# Noctua2.net
KiCad netlist of a schematic drawn in EAGLE
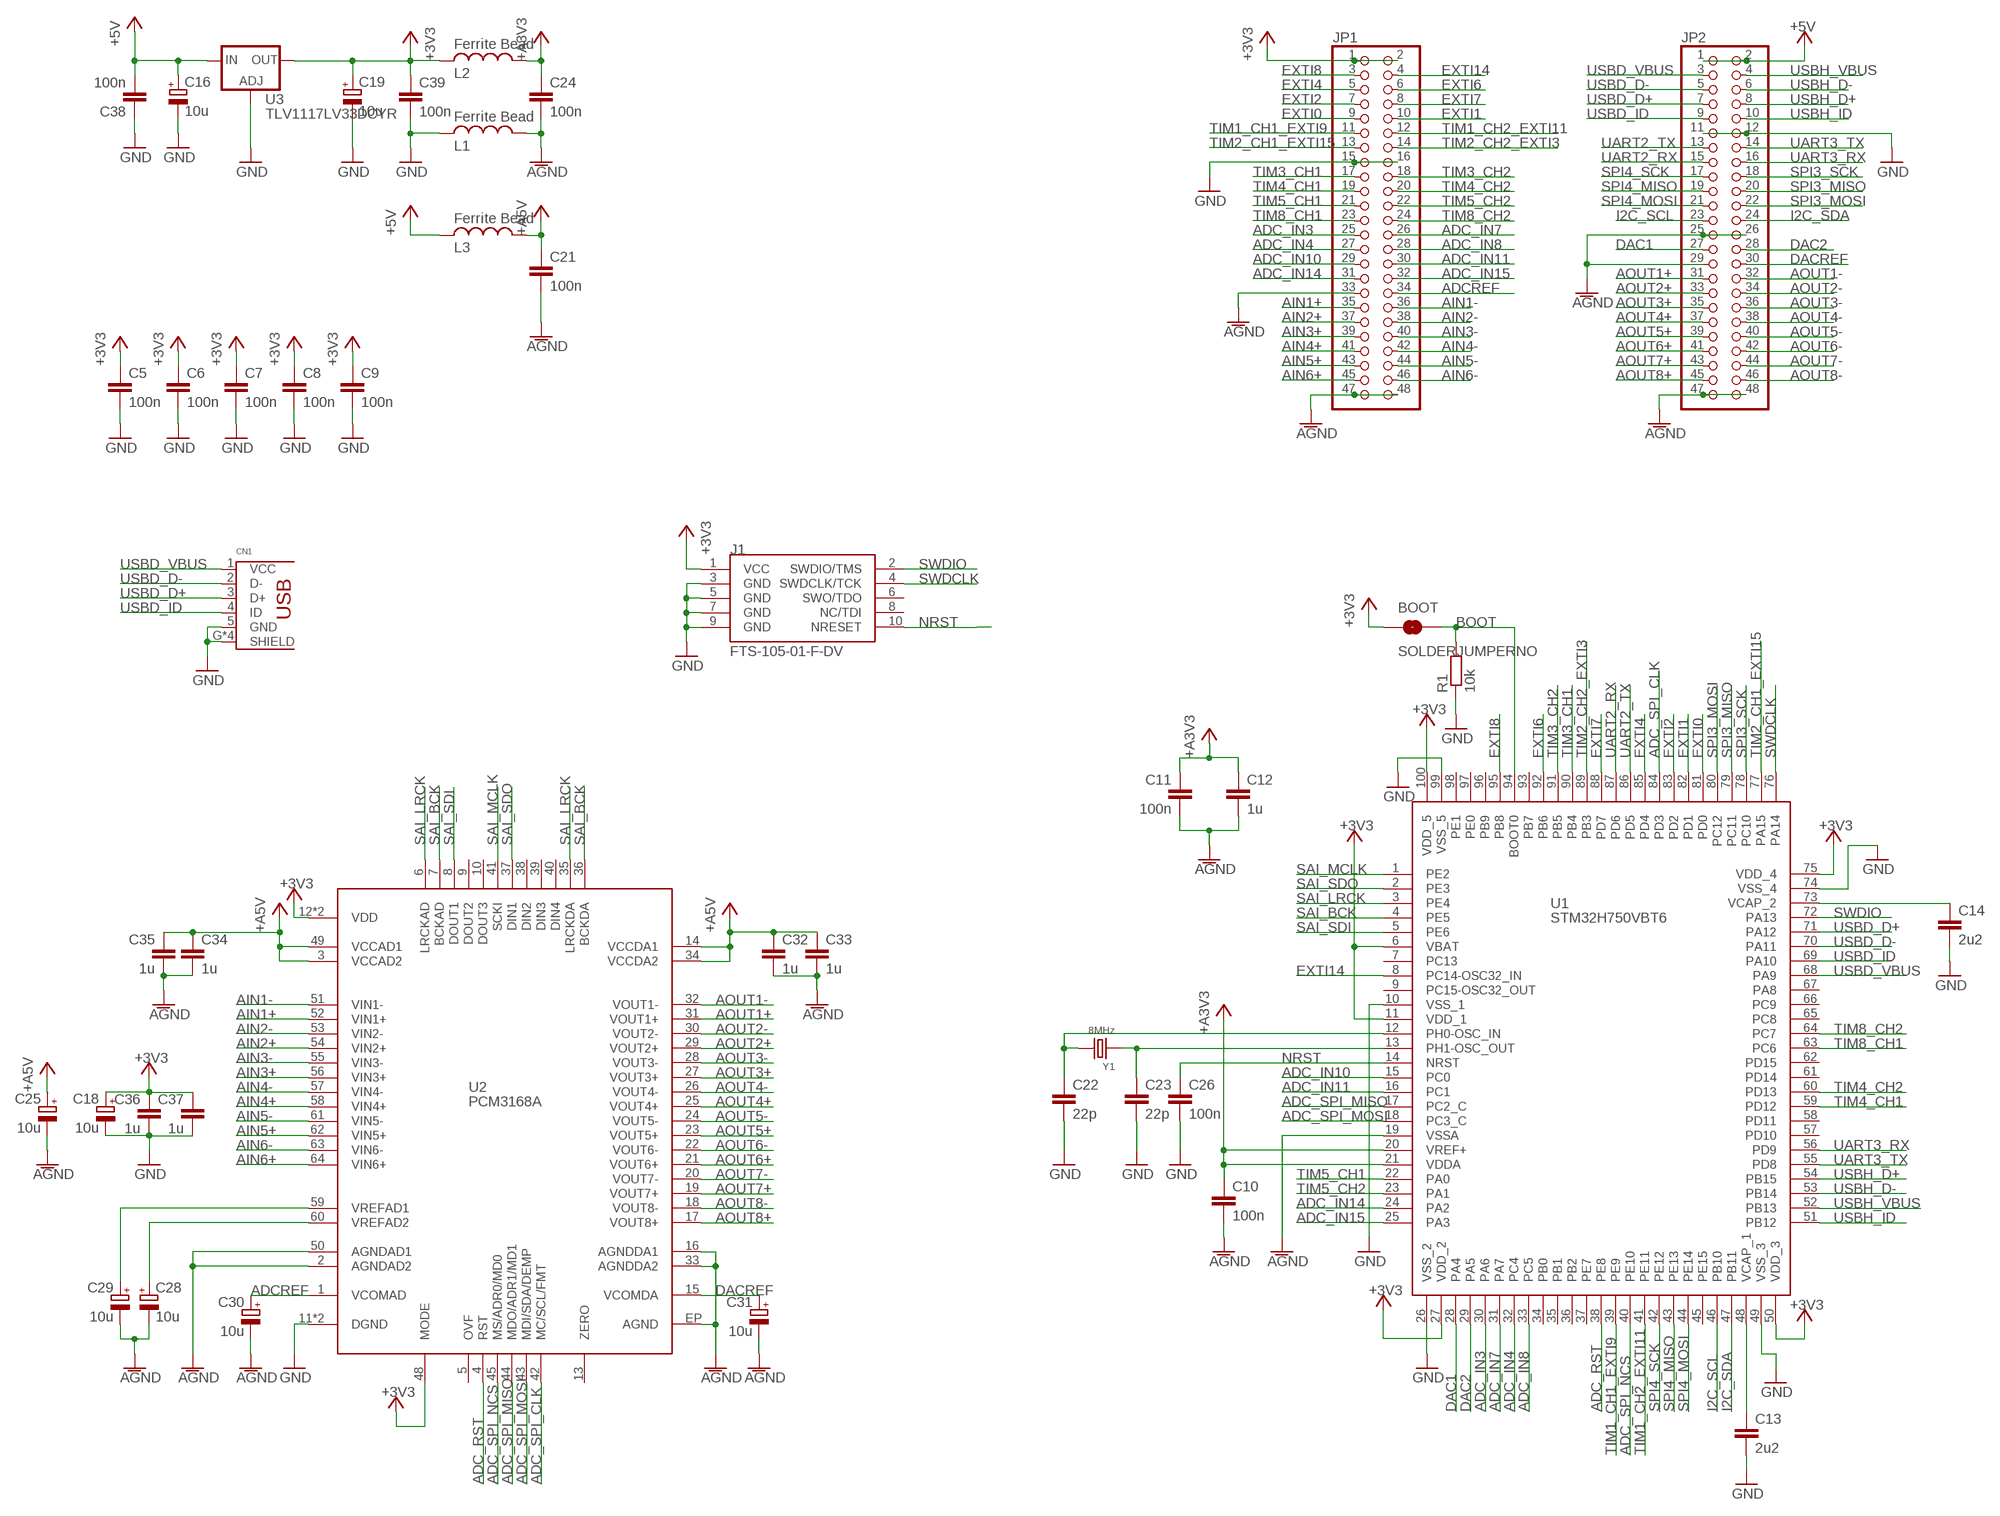
[diagram p0: schematic, sheet 1]

(export (version "E")
  (design (tool "Eeschema 10.0.6"))
  (components
    (comp (ref "BOOT")
      (value "SOLDERJUMPERNO")
      (footprint "eagle-import:SJ_2S-NO")
      (libsource (lib "eagle-import") (part "SOLDERJUMPERNO"))
    )
    (comp (ref "C5")
      (value "100n")
      (footprint "eagle-import:C0603")
      (libsource (lib "eagle-import") (part "C-EUC0603"))
    )
    (comp (ref "C6")
      (value "100n")
      (footprint "eagle-import:C0603")
      (libsource (lib "eagle-import") (part "C-EUC0603"))
    )
    (comp (ref "C7")
      (value "100n")
      (footprint "eagle-import:C0603")
      (libsource (lib "eagle-import") (part "C-EUC0603"))
    )
    (comp (ref "C8")
      (value "100n")
      (footprint "eagle-import:C0603")
      (libsource (lib "eagle-import") (part "C-EUC0603"))
    )
    (comp (ref "C9")
      (value "100n")
      (footprint "eagle-import:C0603")
      (libsource (lib "eagle-import") (part "C-EUC0603"))
    )
    (comp (ref "C10")
      (value "100n")
      (footprint "eagle-import:C0603")
      (libsource (lib "eagle-import") (part "C-EUC0603"))
    )
    (comp (ref "C11")
      (value "100n")
      (footprint "eagle-import:C0603")
      (libsource (lib "eagle-import") (part "C-EUC0603"))
    )
    (comp (ref "C12")
      (value "1u")
      (footprint "eagle-import:C0603")
      (libsource (lib "eagle-import") (part "C-EUC0603"))
    )
    (comp (ref "C13")
      (value "2u2")
      (footprint "eagle-import:C0603")
      (libsource (lib "eagle-import") (part "C-EUC0603"))
    )
    (comp (ref "C14")
      (value "2u2")
      (footprint "eagle-import:C0603")
      (libsource (lib "eagle-import") (part "C-EUC0603"))
    )
    (comp (ref "C16")
      (value "10u")
      (footprint "eagle-import:UD-4X5,8_NICHICON")
      (libsource (lib "eagle-import") (part "CPOL-EUUD-4X5,8"))
    )
    (comp (ref "C18")
      (value "10u")
      (footprint "eagle-import:UD-4X5,8_NICHICON")
      (libsource (lib "eagle-import") (part "CPOL-EUUD-4X5,8"))
    )
    (comp (ref "C19")
      (value "10u")
      (footprint "eagle-import:UD-4X5,8_NICHICON")
      (libsource (lib "eagle-import") (part "CPOL-EUUD-4X5,8"))
    )
    (comp (ref "C21")
      (value "100n")
      (footprint "eagle-import:C0603")
      (libsource (lib "eagle-import") (part "C-EUC0603"))
    )
    (comp (ref "C22")
      (value "22p")
      (footprint "eagle-import:C0603")
      (libsource (lib "eagle-import") (part "C-EUC0603"))
    )
    (comp (ref "C23")
      (value "22p")
      (footprint "eagle-import:C0603")
      (libsource (lib "eagle-import") (part "C-EUC0603"))
    )
    (comp (ref "C24")
      (value "100n")
      (footprint "eagle-import:C0603")
      (libsource (lib "eagle-import") (part "C-EUC0603"))
    )
    (comp (ref "C25")
      (value "10u")
      (footprint "eagle-import:UD-4X5,8_NICHICON")
      (libsource (lib "eagle-import") (part "CPOL-EUUD-4X5,8"))
    )
    (comp (ref "C26")
      (value "100n")
      (footprint "eagle-import:C0603")
      (libsource (lib "eagle-import") (part "C-EUC0603"))
    )
    (comp (ref "C28")
      (value "10u")
      (footprint "eagle-import:UD-4X5,8_NICHICON")
      (libsource (lib "eagle-import") (part "CPOL-EUUD-4X5,8"))
    )
    (comp (ref "C29")
      (value "10u")
      (footprint "eagle-import:UD-4X5,8_NICHICON")
      (libsource (lib "eagle-import") (part "CPOL-EUUD-4X5,8"))
    )
    (comp (ref "C30")
      (value "10u")
      (footprint "eagle-import:UD-4X5,8_NICHICON")
      (libsource (lib "eagle-import") (part "CPOL-EUUD-4X5,8"))
    )
    (comp (ref "C31")
      (value "10u")
      (footprint "eagle-import:UD-4X5,8_NICHICON")
      (libsource (lib "eagle-import") (part "CPOL-EUUD-4X5,8"))
    )
    (comp (ref "C32")
      (value "1u")
      (footprint "eagle-import:C0603")
      (libsource (lib "eagle-import") (part "C-EUC0603"))
    )
    (comp (ref "C33")
      (value "1u")
      (footprint "eagle-import:C0603")
      (libsource (lib "eagle-import") (part "C-EUC0603"))
    )
    (comp (ref "C34")
      (value "1u")
      (footprint "eagle-import:C0603")
      (libsource (lib "eagle-import") (part "C-EUC0603"))
    )
    (comp (ref "C35")
      (value "1u")
      (footprint "eagle-import:C0603")
      (libsource (lib "eagle-import") (part "C-EUC0603"))
    )
    (comp (ref "C36")
      (value "1u")
      (footprint "eagle-import:C0603")
      (libsource (lib "eagle-import") (part "C-EUC0603"))
    )
    (comp (ref "C37")
      (value "1u")
      (footprint "eagle-import:C0603")
      (libsource (lib "eagle-import") (part "C-EUC0603"))
    )
    (comp (ref "C38")
      (value "100n")
      (footprint "eagle-import:C0603")
      (libsource (lib "eagle-import") (part "C-EUC0603"))
    )
    (comp (ref "C39")
      (value "100n")
      (footprint "eagle-import:C0603")
      (libsource (lib "eagle-import") (part "C-EUC0603"))
    )
    (comp (ref "CN1")
      (value "USB_HRS_ZX62-B-5PA(11)MICRO.B")
      (footprint "eagle-import:HRS_ZX62RD-AB-5P8")
      (libsource (lib "eagle-import") (part "USB_HRS_ZX62-B-5PA(11)MICRO.B"))
    )
    (comp (ref "J1")
      (value "FTS-105-01-F-DV")
      (footprint "eagle-import:2X5_1.27MM_SMD")
      (libsource (lib "eagle-import") (part "ARM_10SMD"))
    )
    (comp (ref "JP1")
      (value "PINHD-2X24")
      (footprint "eagle-import:2X24")
      (libsource (lib "eagle-import") (part "PINHD-2X24"))
    )
    (comp (ref "JP2")
      (value "PINHD-2X24")
      (footprint "eagle-import:2X24")
      (libsource (lib "eagle-import") (part "PINHD-2X24"))
    )
    (comp (ref "L1")
      (value "Ferrite Bead")
      (footprint "eagle-import:0603")
      (libsource (lib "eagle-import") (part "INDUCTOR"))
    )
    (comp (ref "L2")
      (value "Ferrite Bead")
      (footprint "eagle-import:0603")
      (libsource (lib "eagle-import") (part "INDUCTOR"))
    )
    (comp (ref "L3")
      (value "Ferrite Bead")
      (footprint "eagle-import:0603")
      (libsource (lib "eagle-import") (part "INDUCTOR"))
    )
    (comp (ref "R1")
      (value "10k")
      (footprint "eagle-import:0603@1")
      (libsource (lib "eagle-import") (part "R-EU_0603"))
    )
    (comp (ref "U1")
      (value "STM32H750VBT6")
      (footprint "eagle-import:QFP50P1600X1600X160-100N")
      (fields (field (name "MOUSER_PART_NUMBER") "511-STM32H750VBT6"))
      (libsource (lib "eagle-import") (part "STM32H750VBT6"))
    )
    (comp (ref "U2")
      (value "PCM3168A")
      (footprint "eagle-import:PQFP64")
      (libsource (lib "eagle-import") (part "PCM3168A"))
    )
    (comp (ref "U3")
      (value "TLV1117LV33DCYR")
      (footprint "eagle-import:SOT223")
      (libsource (lib "eagle-import") (part "LD117A?S33TR"))
    )
    (comp (ref "Y1")
      (value "8MHz")
      (footprint "eagle-import:X2-SMD-5.0X3.2X1.3MM")
      (fields (field (name "MPN") "5032/2P"))
      (libsource (lib "eagle-import") (part "SMD-CRYSTAL-8MHZ-20PF-20PPM(2P-5.0X3.2MM)"))
    )
  )
  (nets
    (net (code "1") (name "+3V3") (class "Default")
      (node (ref "BOOT") (pin "1") (pinfunction "1_1") (pintype "passive"))
      (node (ref "C18") (pin "+") (pinfunction "+_+") (pintype "passive"))
      (node (ref "C19") (pin "+") (pinfunction "+_+") (pintype "passive"))
      (node (ref "C36") (pin "1") (pinfunction "1_1") (pintype "passive"))
      (node (ref "C37") (pin "1") (pinfunction "1_1") (pintype "passive"))
      (node (ref "C39") (pin "1") (pinfunction "1_1") (pintype "passive"))
      (node (ref "C5") (pin "1") (pinfunction "1_1") (pintype "passive"))
      (node (ref "C6") (pin "1") (pinfunction "1_1") (pintype "passive"))
      (node (ref "C7") (pin "1") (pinfunction "1_1") (pintype "passive"))
      (node (ref "C8") (pin "1") (pinfunction "1_1") (pintype "passive"))
      (node (ref "C9") (pin "1") (pinfunction "1_1") (pintype "passive"))
      (node (ref "J1") (pin "1") (pinfunction "VCC_1") (pintype "bidirectional"))
      (node (ref "JP1") (pin "1") (pinfunction "1_1") (pintype "passive"))
      (node (ref "JP1") (pin "2") (pinfunction "2_2") (pintype "passive"))
      (node (ref "L2") (pin "2") (pinfunction "2_2") (pintype "passive"))
      (node (ref "U1") (pin "100") (pinfunction "VDD_5_100") (pintype "bidirectional"))
      (node (ref "U1") (pin "11") (pinfunction "VDD_1_11") (pintype "bidirectional"))
      (node (ref "U1") (pin "27") (pinfunction "VDD_2_27") (pintype "bidirectional"))
      (node (ref "U1") (pin "50") (pinfunction "VDD_3_50") (pintype "bidirectional"))
      (node (ref "U1") (pin "6") (pinfunction "VBAT_6") (pintype "bidirectional"))
      (node (ref "U1") (pin "75") (pinfunction "VDD_4_75") (pintype "bidirectional"))
      (node (ref "U2") (pin "12") (pinfunction "VDD_12") (pintype "bidirectional"))
      (node (ref "U2") (pin "46") (pinfunction "VDD_46") (pintype "bidirectional"))
      (node (ref "U2") (pin "48") (pinfunction "MODE_48") (pintype "bidirectional"))
      (node (ref "U3") (pin "4") (pinfunction "OUT_4") (pintype "passive"))
    )
    (net (code "2") (name "+5V") (class "Default")
      (node (ref "C16") (pin "+") (pinfunction "+_+") (pintype "passive"))
      (node (ref "C38") (pin "2") (pinfunction "2_2") (pintype "passive"))
      (node (ref "JP2") (pin "1") (pinfunction "1_1") (pintype "passive"))
      (node (ref "JP2") (pin "2") (pinfunction "2_2") (pintype "passive"))
      (node (ref "L3") (pin "2") (pinfunction "2_2") (pintype "passive"))
      (node (ref "U3") (pin "3") (pinfunction "IN_3") (pintype "input"))
    )
    (net (code "3") (name "+A3V3") (class "Default")
      (node (ref "C10") (pin "1") (pinfunction "1_1") (pintype "passive"))
      (node (ref "C11") (pin "1") (pinfunction "1_1") (pintype "passive"))
      (node (ref "C12") (pin "1") (pinfunction "1_1") (pintype "passive"))
      (node (ref "C24") (pin "1") (pinfunction "1_1") (pintype "passive"))
      (node (ref "L2") (pin "1") (pinfunction "1_1") (pintype "passive"))
      (node (ref "U1") (pin "20") (pinfunction "VREF+_20") (pintype "bidirectional"))
      (node (ref "U1") (pin "21") (pinfunction "VDDA_21") (pintype "bidirectional"))
    )
    (net (code "4") (name "+A5V") (class "Default")
      (node (ref "C21") (pin "1") (pinfunction "1_1") (pintype "passive"))
      (node (ref "C25") (pin "+") (pinfunction "+_+") (pintype "passive"))
      (node (ref "C32") (pin "1") (pinfunction "1_1") (pintype "passive"))
      (node (ref "C33") (pin "1") (pinfunction "1_1") (pintype "passive"))
      (node (ref "C34") (pin "1") (pinfunction "1_1") (pintype "passive"))
      (node (ref "C35") (pin "1") (pinfunction "1_1") (pintype "passive"))
      (node (ref "L3") (pin "1") (pinfunction "1_1") (pintype "passive"))
      (node (ref "U2") (pin "14") (pinfunction "VCCDA1_14") (pintype "bidirectional"))
      (node (ref "U2") (pin "3") (pinfunction "VCCAD2_3") (pintype "bidirectional"))
      (node (ref "U2") (pin "34") (pinfunction "VCCDA2_34") (pintype "bidirectional"))
      (node (ref "U2") (pin "49") (pinfunction "VCCAD1_49") (pintype "bidirectional"))
    )
    (net (code "5") (name "/ADCREF") (class "Default")
      (node (ref "C30") (pin "+") (pinfunction "+_+") (pintype "passive"))
      (node (ref "JP1") (pin "34") (pinfunction "34_34") (pintype "passive"))
      (node (ref "U2") (pin "1") (pinfunction "VCOMAD_1") (pintype "bidirectional"))
    )
    (net (code "6") (name "/ADC_IN3") (class "Default")
      (node (ref "JP1") (pin "25") (pinfunction "25_25") (pintype "passive"))
      (node (ref "U1") (pin "30") (pinfunction "PA6_30") (pintype "bidirectional"))
    )
    (net (code "7") (name "/ADC_IN4") (class "Default")
      (node (ref "JP1") (pin "27") (pinfunction "27_27") (pintype "passive"))
      (node (ref "U1") (pin "32") (pinfunction "PC4_32") (pintype "bidirectional"))
    )
    (net (code "8") (name "/ADC_IN7") (class "Default")
      (node (ref "JP1") (pin "26") (pinfunction "26_26") (pintype "passive"))
      (node (ref "U1") (pin "31") (pinfunction "PA7_31") (pintype "bidirectional"))
    )
    (net (code "9") (name "/ADC_IN8") (class "Default")
      (node (ref "JP1") (pin "28") (pinfunction "28_28") (pintype "passive"))
      (node (ref "U1") (pin "33") (pinfunction "PC5_33") (pintype "bidirectional"))
    )
    (net (code "10") (name "/ADC_IN10") (class "Default")
      (node (ref "JP1") (pin "29") (pinfunction "29_29") (pintype "passive"))
      (node (ref "U1") (pin "15") (pinfunction "PC0_15") (pintype "bidirectional"))
    )
    (net (code "11") (name "/ADC_IN11") (class "Default")
      (node (ref "JP1") (pin "30") (pinfunction "30_30") (pintype "passive"))
      (node (ref "U1") (pin "16") (pinfunction "PC1_16") (pintype "bidirectional"))
    )
    (net (code "12") (name "/ADC_IN14") (class "Default")
      (node (ref "JP1") (pin "31") (pinfunction "31_31") (pintype "passive"))
      (node (ref "U1") (pin "24") (pinfunction "PA2_24") (pintype "bidirectional"))
    )
    (net (code "13") (name "/ADC_IN15") (class "Default")
      (node (ref "JP1") (pin "32") (pinfunction "32_32") (pintype "passive"))
      (node (ref "U1") (pin "25") (pinfunction "PA3_25") (pintype "bidirectional"))
    )
    (net (code "14") (name "/ADC_RST") (class "Default")
      (node (ref "U1") (pin "38") (pinfunction "PE8_38") (pintype "bidirectional"))
      (node (ref "U2") (pin "4") (pinfunction "RST_4") (pintype "bidirectional"))
    )
    (net (code "15") (name "/ADC_SPI_CLK") (class "Default")
      (node (ref "U1") (pin "84") (pinfunction "PD3_84") (pintype "bidirectional"))
      (node (ref "U2") (pin "42") (pinfunction "MC/SCL/FMT_42") (pintype "bidirectional"))
    )
    (net (code "16") (name "/ADC_SPI_MISO") (class "Default")
      (node (ref "U1") (pin "17") (pinfunction "PC2_C_17") (pintype "bidirectional"))
      (node (ref "U2") (pin "44") (pinfunction "MDO/ADR1/MD1_44") (pintype "bidirectional"))
    )
    (net (code "17") (name "/ADC_SPI_MOSI") (class "Default")
      (node (ref "U1") (pin "18") (pinfunction "PC3_C_18") (pintype "bidirectional"))
      (node (ref "U2") (pin "43") (pinfunction "MDI/SDA/DEMP_43") (pintype "bidirectional"))
    )
    (net (code "18") (name "/ADC_SPI_NCS") (class "Default")
      (node (ref "U1") (pin "40") (pinfunction "PE10_40") (pintype "bidirectional"))
      (node (ref "U2") (pin "45") (pinfunction "MS/ADR0/MD0_45") (pintype "bidirectional"))
    )
    (net (code "19") (name "/AIN1+") (class "Default")
      (node (ref "JP1") (pin "35") (pinfunction "35_35") (pintype "passive"))
      (node (ref "U2") (pin "52") (pinfunction "VIN1+_52") (pintype "bidirectional"))
    )
    (net (code "20") (name "/AIN1-") (class "Default")
      (node (ref "JP1") (pin "36") (pinfunction "36_36") (pintype "passive"))
      (node (ref "U2") (pin "51") (pinfunction "VIN1-_51") (pintype "bidirectional"))
    )
    (net (code "21") (name "/AIN2+") (class "Default")
      (node (ref "JP1") (pin "37") (pinfunction "37_37") (pintype "passive"))
      (node (ref "U2") (pin "54") (pinfunction "VIN2+_54") (pintype "bidirectional"))
    )
    (net (code "22") (name "/AIN2-") (class "Default")
      (node (ref "JP1") (pin "38") (pinfunction "38_38") (pintype "passive"))
      (node (ref "U2") (pin "53") (pinfunction "VIN2-_53") (pintype "bidirectional"))
    )
    (net (code "23") (name "/AIN3+") (class "Default")
      (node (ref "JP1") (pin "39") (pinfunction "39_39") (pintype "passive"))
      (node (ref "U2") (pin "56") (pinfunction "VIN3+_56") (pintype "bidirectional"))
    )
    (net (code "24") (name "/AIN3-") (class "Default")
      (node (ref "JP1") (pin "40") (pinfunction "40_40") (pintype "passive"))
      (node (ref "U2") (pin "55") (pinfunction "VIN3-_55") (pintype "bidirectional"))
    )
    (net (code "25") (name "/AIN4+") (class "Default")
      (node (ref "JP1") (pin "41") (pinfunction "41_41") (pintype "passive"))
      (node (ref "U2") (pin "58") (pinfunction "VIN4+_58") (pintype "bidirectional"))
    )
    (net (code "26") (name "/AIN4-") (class "Default")
      (node (ref "JP1") (pin "42") (pinfunction "42_42") (pintype "passive"))
      (node (ref "U2") (pin "57") (pinfunction "VIN4-_57") (pintype "bidirectional"))
    )
    (net (code "27") (name "/AIN5+") (class "Default")
      (node (ref "JP1") (pin "43") (pinfunction "43_43") (pintype "passive"))
      (node (ref "U2") (pin "62") (pinfunction "VIN5+_62") (pintype "bidirectional"))
    )
    (net (code "28") (name "/AIN5-") (class "Default")
      (node (ref "JP1") (pin "44") (pinfunction "44_44") (pintype "passive"))
      (node (ref "U2") (pin "61") (pinfunction "VIN5-_61") (pintype "bidirectional"))
    )
    (net (code "29") (name "/AIN6+") (class "Default")
      (node (ref "JP1") (pin "45") (pinfunction "45_45") (pintype "passive"))
      (node (ref "U2") (pin "64") (pinfunction "VIN6+_64") (pintype "bidirectional"))
    )
    (net (code "30") (name "/AIN6-") (class "Default")
      (node (ref "JP1") (pin "46") (pinfunction "46_46") (pintype "passive"))
      (node (ref "U2") (pin "63") (pinfunction "VIN6-_63") (pintype "bidirectional"))
    )
    (net (code "31") (name "/AOUT1+") (class "Default")
      (node (ref "JP2") (pin "31") (pinfunction "31_31") (pintype "passive"))
      (node (ref "U2") (pin "31") (pinfunction "VOUT1+_31") (pintype "bidirectional"))
    )
    (net (code "32") (name "/AOUT1-") (class "Default")
      (node (ref "JP2") (pin "32") (pinfunction "32_32") (pintype "passive"))
      (node (ref "U2") (pin "32") (pinfunction "VOUT1-_32") (pintype "bidirectional"))
    )
    (net (code "33") (name "/AOUT2+") (class "Default")
      (node (ref "JP2") (pin "33") (pinfunction "33_33") (pintype "passive"))
      (node (ref "U2") (pin "29") (pinfunction "VOUT2+_29") (pintype "bidirectional"))
    )
    (net (code "34") (name "/AOUT2-") (class "Default")
      (node (ref "JP2") (pin "34") (pinfunction "34_34") (pintype "passive"))
      (node (ref "U2") (pin "30") (pinfunction "VOUT2-_30") (pintype "bidirectional"))
    )
    (net (code "35") (name "/AOUT3+") (class "Default")
      (node (ref "JP2") (pin "35") (pinfunction "35_35") (pintype "passive"))
      (node (ref "U2") (pin "27") (pinfunction "VOUT3+_27") (pintype "bidirectional"))
    )
    (net (code "36") (name "/AOUT3-") (class "Default")
      (node (ref "JP2") (pin "36") (pinfunction "36_36") (pintype "passive"))
      (node (ref "U2") (pin "28") (pinfunction "VOUT3-_28") (pintype "bidirectional"))
    )
    (net (code "37") (name "/AOUT4+") (class "Default")
      (node (ref "JP2") (pin "37") (pinfunction "37_37") (pintype "passive"))
      (node (ref "U2") (pin "25") (pinfunction "VOUT4+_25") (pintype "bidirectional"))
    )
    (net (code "38") (name "/AOUT4-") (class "Default")
      (node (ref "JP2") (pin "38") (pinfunction "38_38") (pintype "passive"))
      (node (ref "U2") (pin "26") (pinfunction "VOUT4-_26") (pintype "bidirectional"))
    )
    (net (code "39") (name "/AOUT5+") (class "Default")
      (node (ref "JP2") (pin "39") (pinfunction "39_39") (pintype "passive"))
      (node (ref "U2") (pin "23") (pinfunction "VOUT5+_23") (pintype "bidirectional"))
    )
    (net (code "40") (name "/AOUT5-") (class "Default")
      (node (ref "JP2") (pin "40") (pinfunction "40_40") (pintype "passive"))
      (node (ref "U2") (pin "24") (pinfunction "VOUT5-_24") (pintype "bidirectional"))
    )
    (net (code "41") (name "/AOUT6+") (class "Default")
      (node (ref "JP2") (pin "41") (pinfunction "41_41") (pintype "passive"))
      (node (ref "U2") (pin "21") (pinfunction "VOUT6+_21") (pintype "bidirectional"))
    )
    (net (code "42") (name "/AOUT6-") (class "Default")
      (node (ref "JP2") (pin "42") (pinfunction "42_42") (pintype "passive"))
      (node (ref "U2") (pin "22") (pinfunction "VOUT6-_22") (pintype "bidirectional"))
    )
    (net (code "43") (name "/AOUT7+") (class "Default")
      (node (ref "JP2") (pin "43") (pinfunction "43_43") (pintype "passive"))
      (node (ref "U2") (pin "19") (pinfunction "VOUT7+_19") (pintype "bidirectional"))
    )
    (net (code "44") (name "/AOUT7-") (class "Default")
      (node (ref "JP2") (pin "44") (pinfunction "44_44") (pintype "passive"))
      (node (ref "U2") (pin "20") (pinfunction "VOUT7-_20") (pintype "bidirectional"))
    )
    (net (code "45") (name "/AOUT8+") (class "Default")
      (node (ref "JP2") (pin "45") (pinfunction "45_45") (pintype "passive"))
      (node (ref "U2") (pin "17") (pinfunction "VOUT8+_17") (pintype "bidirectional"))
    )
    (net (code "46") (name "/AOUT8-") (class "Default")
      (node (ref "JP2") (pin "46") (pinfunction "46_46") (pintype "passive"))
      (node (ref "U2") (pin "18") (pinfunction "VOUT8-_18") (pintype "bidirectional"))
    )
    (net (code "47") (name "/BOOT") (class "Default")
      (node (ref "BOOT") (pin "2") (pinfunction "2_2") (pintype "passive"))
      (node (ref "R1") (pin "2") (pinfunction "2_2") (pintype "passive"))
      (node (ref "U1") (pin "94") (pinfunction "BOOT0_94") (pintype "bidirectional"))
    )
    (net (code "48") (name "/DAC1") (class "Default")
      (node (ref "JP2") (pin "27") (pinfunction "27_27") (pintype "passive"))
      (node (ref "U1") (pin "28") (pinfunction "PA4_28") (pintype "bidirectional"))
    )
    (net (code "49") (name "/DAC2") (class "Default")
      (node (ref "JP2") (pin "28") (pinfunction "28_28") (pintype "passive"))
      (node (ref "U1") (pin "29") (pinfunction "PA5_29") (pintype "bidirectional"))
    )
    (net (code "50") (name "/DACREF") (class "Default")
      (node (ref "C31") (pin "+") (pinfunction "+_+") (pintype "passive"))
      (node (ref "JP2") (pin "30") (pinfunction "30_30") (pintype "passive"))
      (node (ref "U2") (pin "15") (pinfunction "VCOMDA_15") (pintype "bidirectional"))
    )
    (net (code "51") (name "/EXTI0") (class "Default")
      (node (ref "JP1") (pin "9") (pinfunction "9_9") (pintype "passive"))
      (node (ref "U1") (pin "81") (pinfunction "PD0_81") (pintype "bidirectional"))
    )
    (net (code "52") (name "/EXTI1") (class "Default")
      (node (ref "JP1") (pin "10") (pinfunction "10_10") (pintype "passive"))
      (node (ref "U1") (pin "82") (pinfunction "PD1_82") (pintype "bidirectional"))
    )
    (net (code "53") (name "/EXTI2") (class "Default")
      (node (ref "JP1") (pin "7") (pinfunction "7_7") (pintype "passive"))
      (node (ref "U1") (pin "83") (pinfunction "PD2_83") (pintype "bidirectional"))
    )
    (net (code "54") (name "/EXTI4") (class "Default")
      (node (ref "JP1") (pin "5") (pinfunction "5_5") (pintype "passive"))
      (node (ref "U1") (pin "85") (pinfunction "PD4_85") (pintype "bidirectional"))
    )
    (net (code "55") (name "/EXTI6") (class "Default")
      (node (ref "JP1") (pin "6") (pinfunction "6_6") (pintype "passive"))
      (node (ref "U1") (pin "92") (pinfunction "PB6_92") (pintype "bidirectional"))
    )
    (net (code "56") (name "/EXTI7") (class "Default")
      (node (ref "JP1") (pin "8") (pinfunction "8_8") (pintype "passive"))
      (node (ref "U1") (pin "88") (pinfunction "PD7_88") (pintype "bidirectional"))
    )
    (net (code "57") (name "/EXTI8") (class "Default")
      (node (ref "JP1") (pin "3") (pinfunction "3_3") (pintype "passive"))
      (node (ref "U1") (pin "95") (pinfunction "PB8_95") (pintype "bidirectional"))
    )
    (net (code "58") (name "/EXTI14") (class "Default")
      (node (ref "JP1") (pin "4") (pinfunction "4_4") (pintype "passive"))
      (node (ref "U1") (pin "8") (pinfunction "PC14-OSC32_IN_8") (pintype "bidirectional"))
    )
    (net (code "59") (name "/I2C_SCL") (class "Default")
      (node (ref "JP2") (pin "23") (pinfunction "23_23") (pintype "passive"))
      (node (ref "U1") (pin "46") (pinfunction "PB10_46") (pintype "bidirectional"))
    )
    (net (code "60") (name "/I2C_SDA") (class "Default")
      (node (ref "JP2") (pin "24") (pinfunction "24_24") (pintype "passive"))
      (node (ref "U1") (pin "47") (pinfunction "PB11_47") (pintype "bidirectional"))
    )
    (net (code "61") (name "/NRST") (class "Default")
      (node (ref "C26") (pin "1") (pinfunction "1_1") (pintype "passive"))
      (node (ref "J1") (pin "10") (pinfunction "NRESET_10") (pintype "bidirectional"))
      (node (ref "U1") (pin "14") (pinfunction "NRST_14") (pintype "bidirectional"))
    )
    (net (code "62") (name "/SAI_BCK") (class "Default")
      (node (ref "U1") (pin "4") (pinfunction "PE5_4") (pintype "bidirectional"))
      (node (ref "U2") (pin "36") (pinfunction "BCKDA_36") (pintype "bidirectional"))
      (node (ref "U2") (pin "7") (pinfunction "BCKAD_7") (pintype "bidirectional"))
    )
    (net (code "63") (name "/SAI_LRCK") (class "Default")
      (node (ref "U1") (pin "3") (pinfunction "PE4_3") (pintype "bidirectional"))
      (node (ref "U2") (pin "35") (pinfunction "LRCKDA_35") (pintype "bidirectional"))
      (node (ref "U2") (pin "6") (pinfunction "LRCKAD_6") (pintype "bidirectional"))
    )
    (net (code "64") (name "/SAI_MCLK") (class "Default")
      (node (ref "U1") (pin "1") (pinfunction "PE2_1") (pintype "bidirectional"))
      (node (ref "U2") (pin "41") (pinfunction "SCKI_41") (pintype "bidirectional"))
    )
    (net (code "65") (name "/SAI_SDI") (class "Default")
      (node (ref "U1") (pin "5") (pinfunction "PE6_5") (pintype "bidirectional"))
      (node (ref "U2") (pin "8") (pinfunction "DOUT1_8") (pintype "bidirectional"))
    )
    (net (code "66") (name "/SAI_SDO") (class "Default")
      (node (ref "U1") (pin "2") (pinfunction "PE3_2") (pintype "bidirectional"))
      (node (ref "U2") (pin "37") (pinfunction "DIN1_37") (pintype "bidirectional"))
    )
    (net (code "67") (name "/SPI3_MISO") (class "Default")
      (node (ref "JP2") (pin "20") (pinfunction "20_20") (pintype "passive"))
      (node (ref "U1") (pin "79") (pinfunction "PC11_79") (pintype "bidirectional"))
    )
    (net (code "68") (name "/SPI3_MOSI") (class "Default")
      (node (ref "JP2") (pin "22") (pinfunction "22_22") (pintype "passive"))
      (node (ref "U1") (pin "80") (pinfunction "PC12_80") (pintype "bidirectional"))
    )
    (net (code "69") (name "/SPI3_SCK") (class "Default")
      (node (ref "JP2") (pin "18") (pinfunction "18_18") (pintype "passive"))
      (node (ref "U1") (pin "78") (pinfunction "PC10_78") (pintype "bidirectional"))
    )
    (net (code "70") (name "/SPI4_MISO") (class "Default")
      (node (ref "JP2") (pin "19") (pinfunction "19_19") (pintype "passive"))
      (node (ref "U1") (pin "43") (pinfunction "PE13_43") (pintype "bidirectional"))
    )
    (net (code "71") (name "/SPI4_MOSI") (class "Default")
      (node (ref "JP2") (pin "21") (pinfunction "21_21") (pintype "passive"))
      (node (ref "U1") (pin "44") (pinfunction "PE14_44") (pintype "bidirectional"))
    )
    (net (code "72") (name "/SPI4_SCK") (class "Default")
      (node (ref "JP2") (pin "17") (pinfunction "17_17") (pintype "passive"))
      (node (ref "U1") (pin "42") (pinfunction "PE12_42") (pintype "bidirectional"))
    )
    (net (code "73") (name "/SWDCLK") (class "Default")
      (node (ref "J1") (pin "4") (pinfunction "SWDCLK/TCK_4") (pintype "bidirectional"))
      (node (ref "U1") (pin "76") (pinfunction "PA14_76") (pintype "bidirectional"))
    )
    (net (code "74") (name "/SWDIO") (class "Default")
      (node (ref "J1") (pin "2") (pinfunction "SWDIO/TMS_2") (pintype "bidirectional"))
      (node (ref "U1") (pin "72") (pinfunction "PA13_72") (pintype "bidirectional"))
    )
    (net (code "75") (name "/TIM1_CH1_EXTI9") (class "Default")
      (node (ref "JP1") (pin "11") (pinfunction "11_11") (pintype "passive"))
      (node (ref "U1") (pin "39") (pinfunction "PE9_39") (pintype "bidirectional"))
    )
    (net (code "76") (name "/TIM1_CH2_EXTI11") (class "Default")
      (node (ref "JP1") (pin "12") (pinfunction "12_12") (pintype "passive"))
      (node (ref "U1") (pin "41") (pinfunction "PE11_41") (pintype "bidirectional"))
    )
    (net (code "77") (name "/TIM2_CH1_EXTI15") (class "Default")
      (node (ref "JP1") (pin "13") (pinfunction "13_13") (pintype "passive"))
      (node (ref "U1") (pin "77") (pinfunction "PA15_77") (pintype "bidirectional"))
    )
    (net (code "78") (name "/TIM2_CH2_EXTI3") (class "Default")
      (node (ref "JP1") (pin "14") (pinfunction "14_14") (pintype "passive"))
      (node (ref "U1") (pin "89") (pinfunction "PB3_89") (pintype "bidirectional"))
    )
    (net (code "79") (name "/TIM3_CH1") (class "Default")
      (node (ref "JP1") (pin "17") (pinfunction "17_17") (pintype "passive"))
      (node (ref "U1") (pin "90") (pinfunction "PB4_90") (pintype "bidirectional"))
    )
    (net (code "80") (name "/TIM3_CH2") (class "Default")
      (node (ref "JP1") (pin "18") (pinfunction "18_18") (pintype "passive"))
      (node (ref "U1") (pin "91") (pinfunction "PB5_91") (pintype "bidirectional"))
    )
    (net (code "81") (name "/TIM4_CH1") (class "Default")
      (node (ref "JP1") (pin "19") (pinfunction "19_19") (pintype "passive"))
      (node (ref "U1") (pin "59") (pinfunction "PD12_59") (pintype "bidirectional"))
    )
    (net (code "82") (name "/TIM4_CH2") (class "Default")
      (node (ref "JP1") (pin "20") (pinfunction "20_20") (pintype "passive"))
      (node (ref "U1") (pin "60") (pinfunction "PD13_60") (pintype "bidirectional"))
    )
    (net (code "83") (name "/TIM5_CH1") (class "Default")
      (node (ref "JP1") (pin "21") (pinfunction "21_21") (pintype "passive"))
      (node (ref "U1") (pin "22") (pinfunction "PA0_22") (pintype "bidirectional"))
    )
    (net (code "84") (name "/TIM5_CH2") (class "Default")
      (node (ref "JP1") (pin "22") (pinfunction "22_22") (pintype "passive"))
      (node (ref "U1") (pin "23") (pinfunction "PA1_23") (pintype "bidirectional"))
    )
    (net (code "85") (name "/TIM8_CH1") (class "Default")
      (node (ref "JP1") (pin "23") (pinfunction "23_23") (pintype "passive"))
      (node (ref "U1") (pin "63") (pinfunction "PC6_63") (pintype "bidirectional"))
    )
    (net (code "86") (name "/TIM8_CH2") (class "Default")
      (node (ref "JP1") (pin "24") (pinfunction "24_24") (pintype "passive"))
      (node (ref "U1") (pin "64") (pinfunction "PC7_64") (pintype "bidirectional"))
    )
    (net (code "87") (name "/UART2_RX") (class "Default")
      (node (ref "JP2") (pin "15") (pinfunction "15_15") (pintype "passive"))
      (node (ref "U1") (pin "87") (pinfunction "PD6_87") (pintype "bidirectional"))
    )
    (net (code "88") (name "/UART2_TX") (class "Default")
      (node (ref "JP2") (pin "13") (pinfunction "13_13") (pintype "passive"))
      (node (ref "U1") (pin "86") (pinfunction "PD5_86") (pintype "bidirectional"))
    )
    (net (code "89") (name "/UART3_RX") (class "Default")
      (node (ref "JP2") (pin "16") (pinfunction "16_16") (pintype "passive"))
      (node (ref "U1") (pin "56") (pinfunction "PD9_56") (pintype "bidirectional"))
    )
    (net (code "90") (name "/UART3_TX") (class "Default")
      (node (ref "JP2") (pin "14") (pinfunction "14_14") (pintype "passive"))
      (node (ref "U1") (pin "55") (pinfunction "PD8_55") (pintype "bidirectional"))
    )
    (net (code "91") (name "/USBD_D+") (class "Default")
      (node (ref "CN1") (pin "3") (pinfunction "D+_3") (pintype "bidirectional"))
      (node (ref "JP2") (pin "7") (pinfunction "7_7") (pintype "passive"))
      (node (ref "U1") (pin "71") (pinfunction "PA12_71") (pintype "bidirectional"))
    )
    (net (code "92") (name "/USBD_D-") (class "Default")
      (node (ref "CN1") (pin "2") (pinfunction "D-_2") (pintype "bidirectional"))
      (node (ref "JP2") (pin "5") (pinfunction "5_5") (pintype "passive"))
      (node (ref "U1") (pin "70") (pinfunction "PA11_70") (pintype "bidirectional"))
    )
    (net (code "93") (name "/USBD_ID") (class "Default")
      (node (ref "CN1") (pin "4") (pinfunction "ID_4") (pintype "bidirectional"))
      (node (ref "JP2") (pin "9") (pinfunction "9_9") (pintype "passive"))
      (node (ref "U1") (pin "69") (pinfunction "PA10_69") (pintype "bidirectional"))
    )
    (net (code "94") (name "/USBD_VBUS") (class "Default")
      (node (ref "CN1") (pin "1") (pinfunction "VCC_1") (pintype "bidirectional"))
      (node (ref "JP2") (pin "3") (pinfunction "3_3") (pintype "passive"))
      (node (ref "U1") (pin "68") (pinfunction "PA9_68") (pintype "bidirectional"))
    )
    (net (code "95") (name "/USBH_D+") (class "Default")
      (node (ref "JP2") (pin "8") (pinfunction "8_8") (pintype "passive"))
      (node (ref "U1") (pin "54") (pinfunction "PB15_54") (pintype "bidirectional"))
    )
    (net (code "96") (name "/USBH_D-") (class "Default")
      (node (ref "JP2") (pin "6") (pinfunction "6_6") (pintype "passive"))
      (node (ref "U1") (pin "53") (pinfunction "PB14_53") (pintype "bidirectional"))
    )
    (net (code "97") (name "/USBH_ID") (class "Default")
      (node (ref "JP2") (pin "10") (pinfunction "10_10") (pintype "passive"))
      (node (ref "U1") (pin "51") (pinfunction "PB12_51") (pintype "bidirectional"))
    )
    (net (code "98") (name "/USBH_VBUS") (class "Default")
      (node (ref "JP2") (pin "4") (pinfunction "4_4") (pintype "passive"))
      (node (ref "U1") (pin "52") (pinfunction "PB13_52") (pintype "bidirectional"))
    )
    (net (code "99") (name "AGND") (class "Default")
      (node (ref "C10") (pin "2") (pinfunction "2_2") (pintype "passive"))
      (node (ref "C11") (pin "2") (pinfunction "2_2") (pintype "passive"))
      (node (ref "C12") (pin "2") (pinfunction "2_2") (pintype "passive"))
      (node (ref "C21") (pin "2") (pinfunction "2_2") (pintype "passive"))
      (node (ref "C24") (pin "2") (pinfunction "2_2") (pintype "passive"))
      (node (ref "C25") (pin "-") (pinfunction "-_-") (pintype "passive"))
      (node (ref "C28") (pin "-") (pinfunction "-_-") (pintype "passive"))
      (node (ref "C29") (pin "-") (pinfunction "-_-") (pintype "passive"))
      (node (ref "C30") (pin "-") (pinfunction "-_-") (pintype "passive"))
      (node (ref "C31") (pin "-") (pinfunction "-_-") (pintype "passive"))
      (node (ref "C32") (pin "2") (pinfunction "2_2") (pintype "passive"))
      (node (ref "C33") (pin "2") (pinfunction "2_2") (pintype "passive"))
      (node (ref "C34") (pin "2") (pinfunction "2_2") (pintype "passive"))
      (node (ref "C35") (pin "2") (pinfunction "2_2") (pintype "passive"))
      (node (ref "JP1") (pin "33") (pinfunction "33_33") (pintype "passive"))
      (node (ref "JP1") (pin "47") (pinfunction "47_47") (pintype "passive"))
      (node (ref "JP1") (pin "48") (pinfunction "48_48") (pintype "passive"))
      (node (ref "JP2") (pin "25") (pinfunction "25_25") (pintype "passive"))
      (node (ref "JP2") (pin "26") (pinfunction "26_26") (pintype "passive"))
      (node (ref "JP2") (pin "29") (pinfunction "29_29") (pintype "passive"))
      (node (ref "JP2") (pin "47") (pinfunction "47_47") (pintype "passive"))
      (node (ref "JP2") (pin "48") (pinfunction "48_48") (pintype "passive"))
      (node (ref "L1") (pin "1") (pinfunction "1_1") (pintype "passive"))
      (node (ref "U1") (pin "19") (pinfunction "VSSA_19") (pintype "bidirectional"))
      (node (ref "U2") (pin "16") (pinfunction "AGNDDA1_16") (pintype "bidirectional"))
      (node (ref "U2") (pin "2") (pinfunction "AGNDAD2_2") (pintype "bidirectional"))
      (node (ref "U2") (pin "33") (pinfunction "AGNDDA2_33") (pintype "bidirectional"))
      (node (ref "U2") (pin "50") (pinfunction "AGNDAD1_50") (pintype "bidirectional"))
      (node (ref "U2") (pin "EP") (pinfunction "AGND_EP") (pintype "bidirectional"))
    )
    (net (code "100") (name "GND") (class "Default")
      (node (ref "C13") (pin "2") (pinfunction "2_2") (pintype "passive"))
      (node (ref "C14") (pin "2") (pinfunction "2_2") (pintype "passive"))
      (node (ref "C16") (pin "-") (pinfunction "-_-") (pintype "passive"))
      (node (ref "C18") (pin "-") (pinfunction "-_-") (pintype "passive"))
      (node (ref "C19") (pin "-") (pinfunction "-_-") (pintype "passive"))
      (node (ref "C22") (pin "2") (pinfunction "2_2") (pintype "passive"))
      (node (ref "C23") (pin "2") (pinfunction "2_2") (pintype "passive"))
      (node (ref "C26") (pin "2") (pinfunction "2_2") (pintype "passive"))
      (node (ref "C36") (pin "2") (pinfunction "2_2") (pintype "passive"))
      (node (ref "C37") (pin "2") (pinfunction "2_2") (pintype "passive"))
      (node (ref "C38") (pin "1") (pinfunction "1_1") (pintype "passive"))
      (node (ref "C39") (pin "2") (pinfunction "2_2") (pintype "passive"))
      (node (ref "C5") (pin "2") (pinfunction "2_2") (pintype "passive"))
      (node (ref "C6") (pin "2") (pinfunction "2_2") (pintype "passive"))
      (node (ref "C7") (pin "2") (pinfunction "2_2") (pintype "passive"))
      (node (ref "C8") (pin "2") (pinfunction "2_2") (pintype "passive"))
      (node (ref "C9") (pin "2") (pinfunction "2_2") (pintype "passive"))
      (node (ref "CN1") (pin "5") (pinfunction "GND_5") (pintype "bidirectional"))
      (node (ref "CN1") (pin "G") (pinfunction "SHIELD_G") (pintype "bidirectional"))
      (node (ref "CN1") (pin "G2") (pinfunction "SHIELD_G2") (pintype "bidirectional"))
      (node (ref "CN1") (pin "G3") (pinfunction "SHIELD_G3") (pintype "bidirectional"))
      (node (ref "CN1") (pin "G4") (pinfunction "SHIELD_G4") (pintype "bidirectional"))
      (node (ref "J1") (pin "3") (pinfunction "GND_3") (pintype "bidirectional"))
      (node (ref "J1") (pin "5") (pinfunction "GND_5") (pintype "bidirectional"))
      (node (ref "J1") (pin "7") (pinfunction "GND_7") (pintype "bidirectional"))
      (node (ref "J1") (pin "9") (pinfunction "GND_9") (pintype "bidirectional"))
      (node (ref "JP1") (pin "15") (pinfunction "15_15") (pintype "passive"))
      (node (ref "JP1") (pin "16") (pinfunction "16_16") (pintype "passive"))
      (node (ref "JP2") (pin "11") (pinfunction "11_11") (pintype "passive"))
      (node (ref "JP2") (pin "12") (pinfunction "12_12") (pintype "passive"))
      (node (ref "L1") (pin "2") (pinfunction "2_2") (pintype "passive"))
      (node (ref "R1") (pin "1") (pinfunction "1_1") (pintype "passive"))
      (node (ref "U1") (pin "10") (pinfunction "VSS_1_10") (pintype "bidirectional"))
      (node (ref "U1") (pin "26") (pinfunction "VSS_2_26") (pintype "bidirectional"))
      (node (ref "U1") (pin "49") (pinfunction "VSS_3_49") (pintype "bidirectional"))
      (node (ref "U1") (pin "74") (pinfunction "VSS_4_74") (pintype "bidirectional"))
      (node (ref "U1") (pin "99") (pinfunction "VSS_5_99") (pintype "bidirectional"))
      (node (ref "U2") (pin "11") (pinfunction "DGND_11") (pintype "bidirectional"))
      (node (ref "U2") (pin "47") (pinfunction "DGND_47") (pintype "bidirectional"))
      (node (ref "U3") (pin "1") (pinfunction "ADJ_1") (pintype "input"))
    )
    (net (code "101") (name "Net-(U1-PH0-OSC_IN)") (class "Default")
      (node (ref "C22") (pin "1") (pinfunction "1_1") (pintype "passive"))
      (node (ref "U1") (pin "12") (pinfunction "PH0-OSC_IN_12") (pintype "bidirectional"))
      (node (ref "Y1") (pin "2") (pinfunction "2_2") (pintype "passive"))
    )
    (net (code "102") (name "Net-(U1-PH1-OSC_OUT)") (class "Default")
      (node (ref "C23") (pin "1") (pinfunction "1_1") (pintype "passive"))
      (node (ref "U1") (pin "13") (pinfunction "PH1-OSC_OUT_13") (pintype "bidirectional"))
      (node (ref "Y1") (pin "1") (pinfunction "1_1") (pintype "passive"))
    )
    (net (code "103") (name "Net-(U1-VCAP_1)") (class "Default")
      (node (ref "C13") (pin "1") (pinfunction "1_1") (pintype "passive"))
      (node (ref "U1") (pin "48") (pinfunction "VCAP_1_48") (pintype "bidirectional"))
    )
    (net (code "104") (name "Net-(U1-VCAP_2)") (class "Default")
      (node (ref "C14") (pin "1") (pinfunction "1_1") (pintype "passive"))
      (node (ref "U1") (pin "73") (pinfunction "VCAP_2_73") (pintype "bidirectional"))
    )
    (net (code "105") (name "Net-(U2-VREFAD1)") (class "Default")
      (node (ref "C29") (pin "+") (pinfunction "+_+") (pintype "passive"))
      (node (ref "U2") (pin "59") (pinfunction "VREFAD1_59") (pintype "bidirectional"))
    )
    (net (code "106") (name "Net-(U2-VREFAD2)") (class "Default")
      (node (ref "C28") (pin "+") (pinfunction "+_+") (pintype "passive"))
      (node (ref "U2") (pin "60") (pinfunction "VREFAD2_60") (pintype "bidirectional"))
    )
    (net (code "107") (name "unconnected-(J1-NC{slash}TDI-Pad8)") (class "Default")
      (node (ref "J1") (pin "8") (pinfunction "NC/TDI_8") (pintype "bidirectional"))
    )
    (net (code "108") (name "unconnected-(J1-SWO{slash}TDO-Pad6)") (class "Default")
      (node (ref "J1") (pin "6") (pinfunction "SWO/TDO_6") (pintype "bidirectional"))
    )
    (net (code "109") (name "unconnected-(U1-PA8-Pad67)") (class "Default")
      (node (ref "U1") (pin "67") (pinfunction "PA8_67") (pintype "bidirectional"))
    )
    (net (code "110") (name "unconnected-(U1-PB0-Pad34)") (class "Default")
      (node (ref "U1") (pin "34") (pinfunction "PB0_34") (pintype "bidirectional"))
    )
    (net (code "111") (name "unconnected-(U1-PB1-Pad35)") (class "Default")
      (node (ref "U1") (pin "35") (pinfunction "PB1_35") (pintype "bidirectional"))
    )
    (net (code "112") (name "unconnected-(U1-PB2-Pad36)") (class "Default")
      (node (ref "U1") (pin "36") (pinfunction "PB2_36") (pintype "bidirectional"))
    )
    (net (code "113") (name "unconnected-(U1-PB7-Pad93)") (class "Default")
      (node (ref "U1") (pin "93") (pinfunction "PB7_93") (pintype "bidirectional"))
    )
    (net (code "114") (name "unconnected-(U1-PB9-Pad96)") (class "Default")
      (node (ref "U1") (pin "96") (pinfunction "PB9_96") (pintype "bidirectional"))
    )
    (net (code "115") (name "unconnected-(U1-PC8-Pad65)") (class "Default")
      (node (ref "U1") (pin "65") (pinfunction "PC8_65") (pintype "bidirectional"))
    )
    (net (code "116") (name "unconnected-(U1-PC9-Pad66)") (class "Default")
      (node (ref "U1") (pin "66") (pinfunction "PC9_66") (pintype "bidirectional"))
    )
    (net (code "117") (name "unconnected-(U1-PC13-Pad7)") (class "Default")
      (node (ref "U1") (pin "7") (pinfunction "PC13_7") (pintype "bidirectional"))
    )
    (net (code "118") (name "unconnected-(U1-PC15-OSC32_OUT-Pad9)") (class "Default")
      (node (ref "U1") (pin "9") (pinfunction "PC15-OSC32_OUT_9") (pintype "bidirectional"))
    )
    (net (code "119") (name "unconnected-(U1-PD10-Pad57)") (class "Default")
      (node (ref "U1") (pin "57") (pinfunction "PD10_57") (pintype "bidirectional"))
    )
    (net (code "120") (name "unconnected-(U1-PD11-Pad58)") (class "Default")
      (node (ref "U1") (pin "58") (pinfunction "PD11_58") (pintype "bidirectional"))
    )
    (net (code "121") (name "unconnected-(U1-PD14-Pad61)") (class "Default")
      (node (ref "U1") (pin "61") (pinfunction "PD14_61") (pintype "bidirectional"))
    )
    (net (code "122") (name "unconnected-(U1-PD15-Pad62)") (class "Default")
      (node (ref "U1") (pin "62") (pinfunction "PD15_62") (pintype "bidirectional"))
    )
    (net (code "123") (name "unconnected-(U1-PE0-Pad97)") (class "Default")
      (node (ref "U1") (pin "97") (pinfunction "PE0_97") (pintype "bidirectional"))
    )
    (net (code "124") (name "unconnected-(U1-PE1-Pad98)") (class "Default")
      (node (ref "U1") (pin "98") (pinfunction "PE1_98") (pintype "bidirectional"))
    )
    (net (code "125") (name "unconnected-(U1-PE7-Pad37)") (class "Default")
      (node (ref "U1") (pin "37") (pinfunction "PE7_37") (pintype "bidirectional"))
    )
    (net (code "126") (name "unconnected-(U1-PE15-Pad45)") (class "Default")
      (node (ref "U1") (pin "45") (pinfunction "PE15_45") (pintype "bidirectional"))
    )
    (net (code "127") (name "unconnected-(U2-DIN2-Pad38)") (class "Default")
      (node (ref "U2") (pin "38") (pinfunction "DIN2_38") (pintype "bidirectional"))
    )
    (net (code "128") (name "unconnected-(U2-DIN3-Pad39)") (class "Default")
      (node (ref "U2") (pin "39") (pinfunction "DIN3_39") (pintype "bidirectional"))
    )
    (net (code "129") (name "unconnected-(U2-DIN4-Pad40)") (class "Default")
      (node (ref "U2") (pin "40") (pinfunction "DIN4_40") (pintype "bidirectional"))
    )
    (net (code "130") (name "unconnected-(U2-DOUT2-Pad9)") (class "Default")
      (node (ref "U2") (pin "9") (pinfunction "DOUT2_9") (pintype "bidirectional"))
    )
    (net (code "131") (name "unconnected-(U2-DOUT3-Pad10)") (class "Default")
      (node (ref "U2") (pin "10") (pinfunction "DOUT3_10") (pintype "bidirectional"))
    )
    (net (code "132") (name "unconnected-(U2-OVF-Pad5)") (class "Default")
      (node (ref "U2") (pin "5") (pinfunction "OVF_5") (pintype "bidirectional"))
    )
    (net (code "133") (name "unconnected-(U2-ZERO-Pad13)") (class "Default")
      (node (ref "U2") (pin "13") (pinfunction "ZERO_13") (pintype "bidirectional"))
    )
  )
)
